# leds.net
KiCad netlist of a schematic drawn in EAGLE
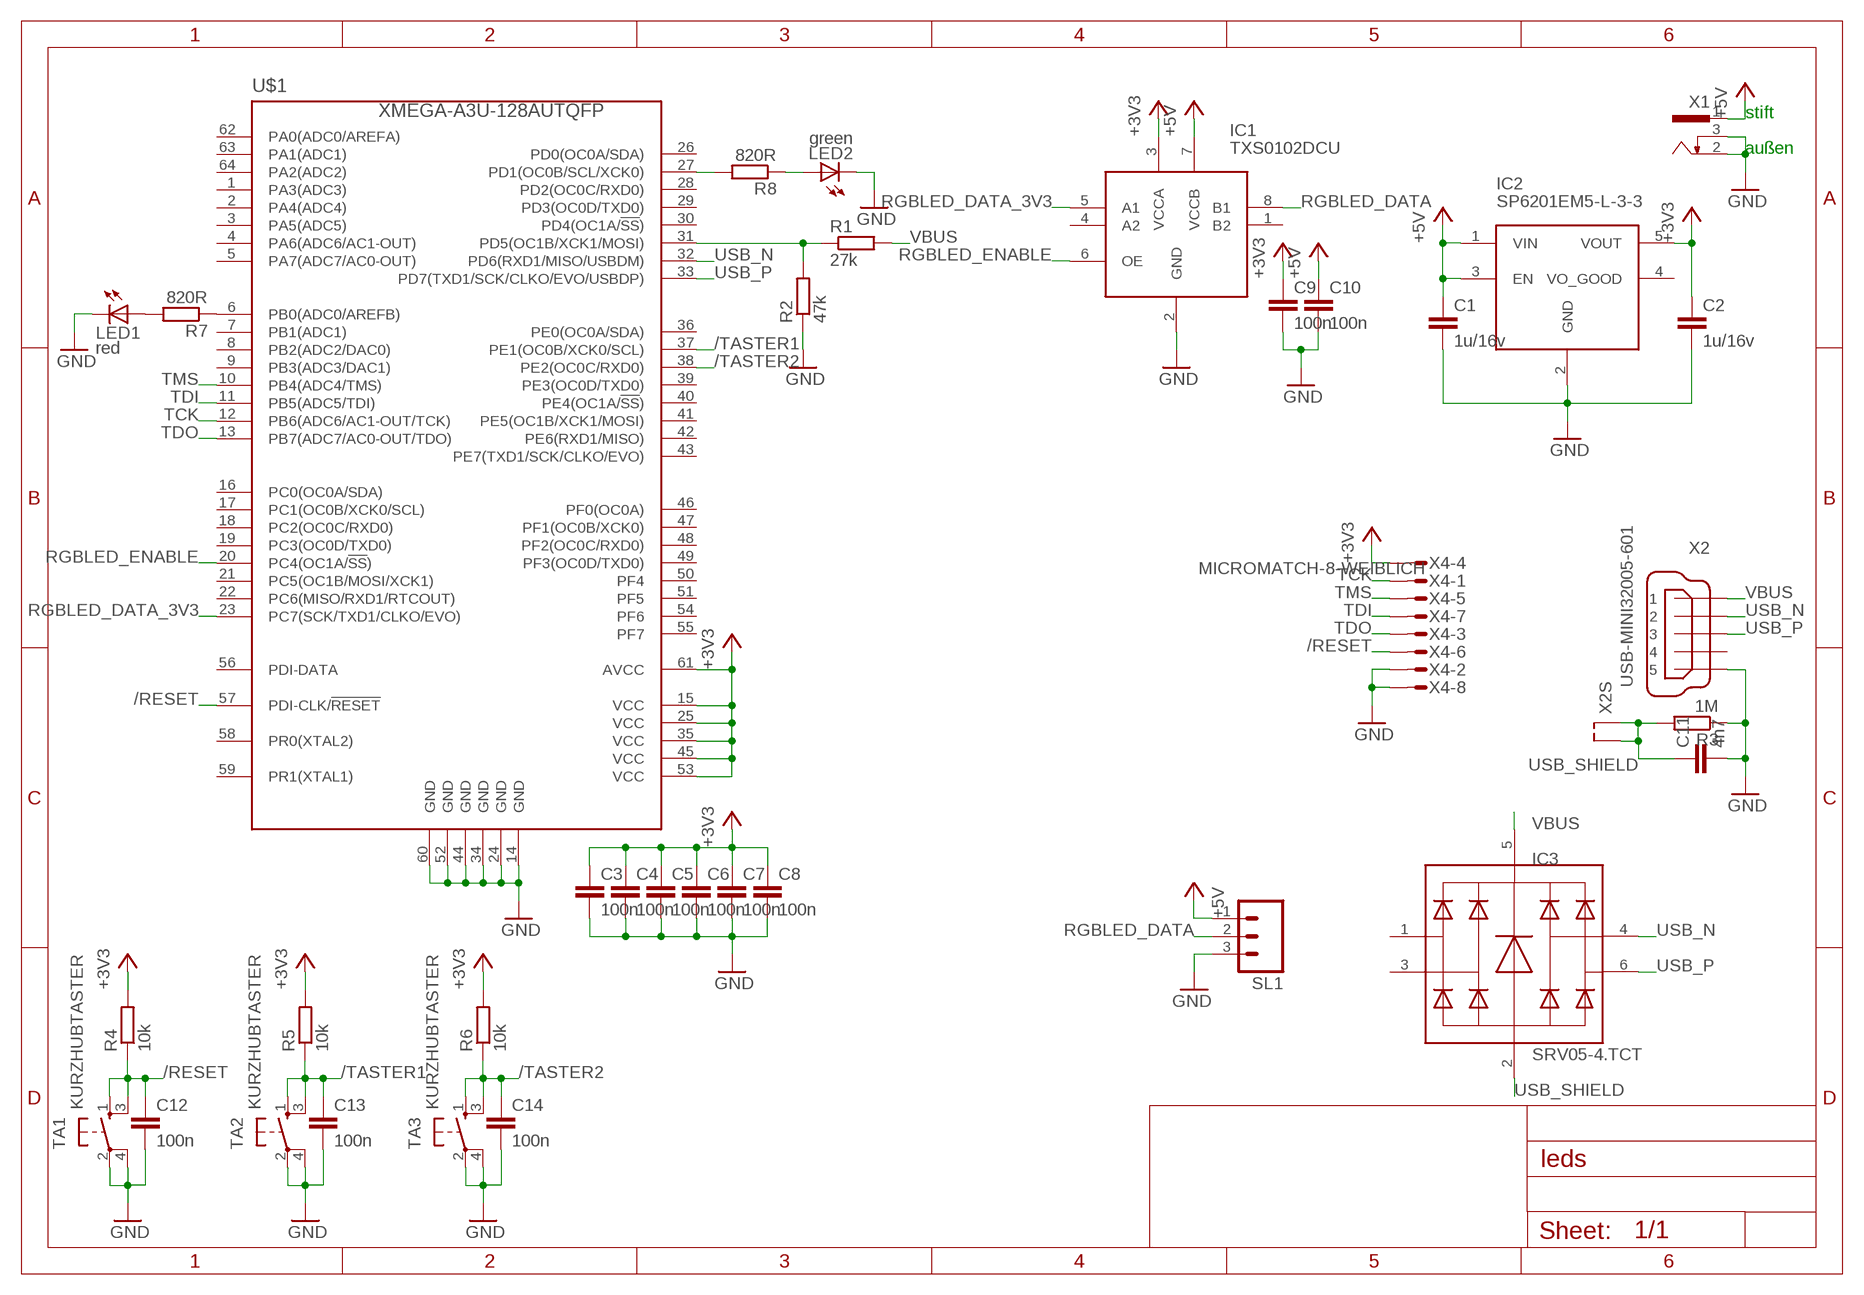
[diagram p0: schematic, sheet 1]

(export (version "E")
  (design (tool "Eeschema 10.0.6"))
  (components
    (comp (ref "C1")
      (value "1u/16v")
      (footprint "eagle-import:C0603")
      (libsource (lib "eagle-import") (part "C-EUC0603"))
    )
    (comp (ref "C2")
      (value "1u/16v")
      (footprint "eagle-import:C0603")
      (libsource (lib "eagle-import") (part "C-EUC0603"))
    )
    (comp (ref "C3")
      (value "100n")
      (footprint "eagle-import:C0603")
      (libsource (lib "eagle-import") (part "C-EUC0603"))
    )
    (comp (ref "C4")
      (value "100n")
      (footprint "eagle-import:C0603")
      (libsource (lib "eagle-import") (part "C-EUC0603"))
    )
    (comp (ref "C5")
      (value "100n")
      (footprint "eagle-import:C0603")
      (libsource (lib "eagle-import") (part "C-EUC0603"))
    )
    (comp (ref "C6")
      (value "100n")
      (footprint "eagle-import:C0603")
      (libsource (lib "eagle-import") (part "C-EUC0603"))
    )
    (comp (ref "C7")
      (value "100n")
      (footprint "eagle-import:C0603")
      (libsource (lib "eagle-import") (part "C-EUC0603"))
    )
    (comp (ref "C8")
      (value "100n")
      (footprint "eagle-import:C0603")
      (libsource (lib "eagle-import") (part "C-EUC0603"))
    )
    (comp (ref "C9")
      (value "100n")
      (footprint "eagle-import:C0603")
      (libsource (lib "eagle-import") (part "C-EUC0603"))
    )
    (comp (ref "C10")
      (value "100n")
      (footprint "eagle-import:C0603")
      (libsource (lib "eagle-import") (part "C-EUC0603"))
    )
    (comp (ref "C11")
      (value "4n7")
      (footprint "eagle-import:C0603")
      (libsource (lib "eagle-import") (part "C-EUC0603"))
    )
    (comp (ref "C12")
      (value "100n")
      (footprint "eagle-import:C0603")
      (libsource (lib "eagle-import") (part "C-EUC0603"))
    )
    (comp (ref "C13")
      (value "100n")
      (footprint "eagle-import:C0603")
      (libsource (lib "eagle-import") (part "C-EUC0603"))
    )
    (comp (ref "C14")
      (value "100n")
      (footprint "eagle-import:C0603")
      (libsource (lib "eagle-import") (part "C-EUC0603"))
    )
    (comp (ref "IC1")
      (value "TXS0102DCU")
      (footprint "eagle-import:DCU8")
      (libsource (lib "eagle-import") (part "TXS0102DCU"))
    )
    (comp (ref "IC2")
      (value "SP6201EM5-L-3-3")
      (footprint "eagle-import:SOT23-5")
      (libsource (lib "eagle-import") (part "SP6201EM5-L-3-3"))
    )
    (comp (ref "IC3")
      (value "SRV05-4.TCT")
      (footprint "eagle-import:SOT23-6")
      (libsource (lib "eagle-import") (part "SRV05-4.TCT"))
    )
    (comp (ref "LED1")
      (value "red")
      (footprint "eagle-import:CHIPLED_0603")
      (libsource (lib "eagle-import") (part "LEDCHIPLED_0603LR"))
    )
    (comp (ref "LED2")
      (value "green")
      (footprint "eagle-import:CHIPLED_0603")
      (libsource (lib "eagle-import") (part "LEDCHIPLED_0603LG"))
    )
    (comp (ref "R1")
      (value "27k")
      (footprint "eagle-import:R0603")
      (libsource (lib "eagle-import") (part "R-EU_R0603"))
    )
    (comp (ref "R2")
      (value "47k")
      (footprint "eagle-import:R0603")
      (libsource (lib "eagle-import") (part "R-EU_R0603"))
    )
    (comp (ref "R3")
      (value "1M")
      (footprint "eagle-import:R0603")
      (libsource (lib "eagle-import") (part "R-EU_R0603"))
    )
    (comp (ref "R4")
      (value "10k")
      (footprint "eagle-import:R0603")
      (libsource (lib "eagle-import") (part "R-EU_R0603"))
    )
    (comp (ref "R5")
      (value "10k")
      (footprint "eagle-import:R0603")
      (libsource (lib "eagle-import") (part "R-EU_R0603"))
    )
    (comp (ref "R6")
      (value "10k")
      (footprint "eagle-import:R0603")
      (libsource (lib "eagle-import") (part "R-EU_R0603"))
    )
    (comp (ref "R7")
      (value "820R")
      (footprint "eagle-import:R0603")
      (libsource (lib "eagle-import") (part "R-EU_R0603"))
    )
    (comp (ref "R8")
      (value "820R")
      (footprint "eagle-import:R0603")
      (libsource (lib "eagle-import") (part "R-EU_R0603"))
    )
    (comp (ref "SL1")
      (value "M03")
      (footprint "eagle-import:03P")
      (libsource (lib "eagle-import") (part "M03"))
    )
    (comp (ref "TA1")
      (value "KURZHUBTASTER")
      (footprint "eagle-import:TA93XX")
      (libsource (lib "eagle-import") (part "KURZHUBTASTER"))
    )
    (comp (ref "TA2")
      (value "KURZHUBTASTER")
      (footprint "eagle-import:TA93XX")
      (libsource (lib "eagle-import") (part "KURZHUBTASTER"))
    )
    (comp (ref "TA3")
      (value "KURZHUBTASTER")
      (footprint "eagle-import:TA93XX")
      (libsource (lib "eagle-import") (part "KURZHUBTASTER"))
    )
    (comp (ref "U$1")
      (value "XMEGA-A3U-128AUTQFP")
      (footprint "eagle-import:TQFP64")
      (libsource (lib "eagle-import") (part "XMEGA-A3UTQFP-128AU"))
    )
    (comp (ref "X1")
      (value "733980-62")
      (footprint "eagle-import:733980-62")
      (libsource (lib "eagle-import") (part "73398?0-62"))
    )
    (comp (ref "X2")
      (value "USB-MINI32005-601")
      (footprint "eagle-import:32005-601")
      (libsource (lib "eagle-import") (part "USB-MINI32005-601"))
    )
    (comp (ref "X4")
      (value "MICROMATCH-8-WEIBLICH")
      (footprint "eagle-import:MICROMATCH-8")
      (libsource (lib "eagle-import") (part "MICROMATCH-8-WEIBLICH"))
    )
  )
  (nets
    (net (code "1") (name "+3V3") (class "Default")
      (node (ref "C2") (pin "1") (pinfunction "1_1") (pintype "passive"))
      (node (ref "C3") (pin "1") (pinfunction "1_1") (pintype "passive"))
      (node (ref "C4") (pin "1") (pinfunction "1_1") (pintype "passive"))
      (node (ref "C5") (pin "1") (pinfunction "1_1") (pintype "passive"))
      (node (ref "C6") (pin "1") (pinfunction "1_1") (pintype "passive"))
      (node (ref "C7") (pin "1") (pinfunction "1_1") (pintype "passive"))
      (node (ref "C8") (pin "1") (pinfunction "1_1") (pintype "passive"))
      (node (ref "C9") (pin "1") (pinfunction "1_1") (pintype "passive"))
      (node (ref "IC1") (pin "3") (pinfunction "VCCA_3") (pintype "power_in"))
      (node (ref "IC2") (pin "5") (pinfunction "VOUT_5") (pintype "power_in"))
      (node (ref "R4") (pin "2") (pinfunction "2_2") (pintype "passive"))
      (node (ref "R5") (pin "2") (pinfunction "2_2") (pintype "passive"))
      (node (ref "R6") (pin "2") (pinfunction "2_2") (pintype "passive"))
      (node (ref "U$1") (pin "15") (pinfunction "VCC_15") (pintype "power_in"))
      (node (ref "U$1") (pin "25") (pinfunction "VCC_25") (pintype "power_in"))
      (node (ref "U$1") (pin "35") (pinfunction "VCC_35") (pintype "power_in"))
      (node (ref "U$1") (pin "45") (pinfunction "VCC_45") (pintype "power_in"))
      (node (ref "U$1") (pin "53") (pinfunction "VCC_53") (pintype "power_in"))
      (node (ref "U$1") (pin "61") (pinfunction "AVCC_61") (pintype "power_in"))
      (node (ref "X4") (pin "4") (pinfunction "S_4") (pintype "passive"))
    )
    (net (code "2") (name "+5V") (class "Default")
      (node (ref "C1") (pin "1") (pinfunction "1_1") (pintype "passive"))
      (node (ref "C10") (pin "1") (pinfunction "1_1") (pintype "passive"))
      (node (ref "IC1") (pin "7") (pinfunction "VCCB_7") (pintype "power_in"))
      (node (ref "IC2") (pin "1") (pinfunction "VIN_1") (pintype "power_in"))
      (node (ref "IC2") (pin "3") (pinfunction "EN_3") (pintype "input"))
      (node (ref "SL1") (pin "1") (pinfunction "1_1") (pintype "passive"))
      (node (ref "X1") (pin "1") (pinfunction "1_1") (pintype "passive"))
    )
    (net (code "3") (name "/RGBLED_DATA") (class "Default")
      (node (ref "IC1") (pin "8") (pinfunction "B1_8") (pintype "bidirectional"))
      (node (ref "SL1") (pin "2") (pinfunction "2_2") (pintype "passive"))
    )
    (net (code "4") (name "/RGBLED_DATA_3V3") (class "Default")
      (node (ref "IC1") (pin "5") (pinfunction "A1_5") (pintype "bidirectional"))
      (node (ref "U$1") (pin "23") (pinfunction "PC7(SCK/TXD1/CLKO/EVO)_23") (pintype "bidirectional"))
    )
    (net (code "5") (name "/RGBLED_ENABLE") (class "Default")
      (node (ref "IC1") (pin "6") (pinfunction "OE_6") (pintype "input"))
      (node (ref "U$1") (pin "20") (pinfunction "PC4(OC1A/~{SS})_20") (pintype "bidirectional"))
    )
    (net (code "6") (name "/TCK") (class "Default")
      (node (ref "U$1") (pin "12") (pinfunction "PB6(ADC6/AC1-OUT/TCK)_12") (pintype "bidirectional"))
      (node (ref "X4") (pin "1") (pinfunction "S_1") (pintype "passive"))
    )
    (net (code "7") (name "/TDI") (class "Default")
      (node (ref "U$1") (pin "11") (pinfunction "PB5(ADC5/TDI)_11") (pintype "bidirectional"))
      (node (ref "X4") (pin "7") (pinfunction "S_7") (pintype "passive"))
    )
    (net (code "8") (name "/TDO") (class "Default")
      (node (ref "U$1") (pin "13") (pinfunction "PB7(ADC7/AC0-OUT/TDO)_13") (pintype "bidirectional"))
      (node (ref "X4") (pin "3") (pinfunction "S_3") (pintype "passive"))
    )
    (net (code "9") (name "/TMS") (class "Default")
      (node (ref "U$1") (pin "10") (pinfunction "PB4(ADC4/TMS)_10") (pintype "bidirectional"))
      (node (ref "X4") (pin "5") (pinfunction "S_5") (pintype "passive"))
    )
    (net (code "10") (name "/USB_N") (class "Default")
      (node (ref "IC3") (pin "4") (pinfunction "3_4") (pintype "passive"))
      (node (ref "U$1") (pin "32") (pinfunction "PD6(RXD1/MISO/USBDM)_32") (pintype "bidirectional"))
      (node (ref "X2") (pin "2") (pinfunction "2_2") (pintype "passive"))
    )
    (net (code "11") (name "/USB_P") (class "Default")
      (node (ref "IC3") (pin "6") (pinfunction "4_6") (pintype "passive"))
      (node (ref "U$1") (pin "33") (pinfunction "PD7(TXD1/SCK/CLKO/EVO/USBDP)_33") (pintype "bidirectional"))
      (node (ref "X2") (pin "3") (pinfunction "3_3") (pintype "passive"))
    )
    (net (code "12") (name "/USB_SHIELD") (class "Default")
      (node (ref "C11") (pin "1") (pinfunction "1_1") (pintype "passive"))
      (node (ref "IC3") (pin "2") (pinfunction "A_2") (pintype "passive"))
      (node (ref "R3") (pin "2") (pinfunction "2_2") (pintype "passive"))
      (node (ref "X2") (pin "M1") (pinfunction "S1_M1") (pintype "passive"))
      (node (ref "X2") (pin "M2") (pinfunction "S2_M2") (pintype "passive"))
    )
    (net (code "13") (name "/VBUS") (class "Default")
      (node (ref "IC3") (pin "5") (pinfunction "K_5") (pintype "passive"))
      (node (ref "R1") (pin "2") (pinfunction "2_2") (pintype "passive"))
      (node (ref "X2") (pin "1") (pinfunction "1_1") (pintype "passive"))
    )
    (net (code "14") (name "/{slash}RESET") (class "Default")
      (node (ref "C12") (pin "1") (pinfunction "1_1") (pintype "passive"))
      (node (ref "R4") (pin "1") (pinfunction "1_1") (pintype "passive"))
      (node (ref "TA1") (pin "1") (pinfunction "S_1") (pintype "passive"))
      (node (ref "TA1") (pin "3") (pinfunction "S1_3") (pintype "passive"))
      (node (ref "U$1") (pin "57") (pinfunction "PDI-CLK/~{RESET}_57") (pintype "input"))
      (node (ref "X4") (pin "6") (pinfunction "S_6") (pintype "passive"))
    )
    (net (code "15") (name "/{slash}TASTER1") (class "Default")
      (node (ref "C13") (pin "1") (pinfunction "1_1") (pintype "passive"))
      (node (ref "R5") (pin "1") (pinfunction "1_1") (pintype "passive"))
      (node (ref "TA2") (pin "1") (pinfunction "S_1") (pintype "passive"))
      (node (ref "TA2") (pin "3") (pinfunction "S1_3") (pintype "passive"))
      (node (ref "U$1") (pin "37") (pinfunction "PE1(OC0B/XCK0/SCL)_37") (pintype "bidirectional"))
    )
    (net (code "16") (name "/{slash}TASTER2") (class "Default")
      (node (ref "C14") (pin "1") (pinfunction "1_1") (pintype "passive"))
      (node (ref "R6") (pin "1") (pinfunction "1_1") (pintype "passive"))
      (node (ref "TA3") (pin "1") (pinfunction "S_1") (pintype "passive"))
      (node (ref "TA3") (pin "3") (pinfunction "S1_3") (pintype "passive"))
      (node (ref "U$1") (pin "38") (pinfunction "PE2(OC0C/RXD0)_38") (pintype "bidirectional"))
    )
    (net (code "17") (name "GND") (class "Default")
      (node (ref "C1") (pin "2") (pinfunction "2_2") (pintype "passive"))
      (node (ref "C10") (pin "2") (pinfunction "2_2") (pintype "passive"))
      (node (ref "C11") (pin "2") (pinfunction "2_2") (pintype "passive"))
      (node (ref "C12") (pin "2") (pinfunction "2_2") (pintype "passive"))
      (node (ref "C13") (pin "2") (pinfunction "2_2") (pintype "passive"))
      (node (ref "C14") (pin "2") (pinfunction "2_2") (pintype "passive"))
      (node (ref "C2") (pin "2") (pinfunction "2_2") (pintype "passive"))
      (node (ref "C3") (pin "2") (pinfunction "2_2") (pintype "passive"))
      (node (ref "C4") (pin "2") (pinfunction "2_2") (pintype "passive"))
      (node (ref "C5") (pin "2") (pinfunction "2_2") (pintype "passive"))
      (node (ref "C6") (pin "2") (pinfunction "2_2") (pintype "passive"))
      (node (ref "C7") (pin "2") (pinfunction "2_2") (pintype "passive"))
      (node (ref "C8") (pin "2") (pinfunction "2_2") (pintype "passive"))
      (node (ref "C9") (pin "2") (pinfunction "2_2") (pintype "passive"))
      (node (ref "IC1") (pin "2") (pinfunction "GND_2") (pintype "power_in"))
      (node (ref "IC2") (pin "2") (pinfunction "GND_2") (pintype "power_in"))
      (node (ref "LED1") (pin "C") (pinfunction "C_C") (pintype "passive"))
      (node (ref "LED2") (pin "C") (pinfunction "C_C") (pintype "passive"))
      (node (ref "R2") (pin "1") (pinfunction "1_1") (pintype "passive"))
      (node (ref "R3") (pin "1") (pinfunction "1_1") (pintype "passive"))
      (node (ref "SL1") (pin "3") (pinfunction "3_3") (pintype "passive"))
      (node (ref "TA1") (pin "2") (pinfunction "P_2") (pintype "passive"))
      (node (ref "TA1") (pin "4") (pinfunction "P1_4") (pintype "passive"))
      (node (ref "TA2") (pin "2") (pinfunction "P_2") (pintype "passive"))
      (node (ref "TA2") (pin "4") (pinfunction "P1_4") (pintype "passive"))
      (node (ref "TA3") (pin "2") (pinfunction "P_2") (pintype "passive"))
      (node (ref "TA3") (pin "4") (pinfunction "P1_4") (pintype "passive"))
      (node (ref "U$1") (pin "14") (pinfunction "GND_14") (pintype "power_in"))
      (node (ref "U$1") (pin "24") (pinfunction "GND_24") (pintype "power_in"))
      (node (ref "U$1") (pin "34") (pinfunction "GND_34") (pintype "power_in"))
      (node (ref "U$1") (pin "44") (pinfunction "GND_44") (pintype "power_in"))
      (node (ref "U$1") (pin "52") (pinfunction "GND_52") (pintype "power_in"))
      (node (ref "U$1") (pin "60") (pinfunction "GND_60") (pintype "power_in"))
      (node (ref "X1") (pin "2") (pinfunction "2_2") (pintype "passive"))
      (node (ref "X1") (pin "3") (pinfunction "3_3") (pintype "passive"))
      (node (ref "X2") (pin "5") (pinfunction "5_5") (pintype "passive"))
      (node (ref "X4") (pin "2") (pinfunction "S_2") (pintype "passive"))
      (node (ref "X4") (pin "8") (pinfunction "S_8") (pintype "passive"))
    )
    (net (code "18") (name "Net-(LED1-PadA)") (class "Default")
      (node (ref "LED1") (pin "A") (pinfunction "A_A") (pintype "passive"))
      (node (ref "R7") (pin "2") (pinfunction "2_2") (pintype "passive"))
    )
    (net (code "19") (name "Net-(LED2-PadA)") (class "Default")
      (node (ref "LED2") (pin "A") (pinfunction "A_A") (pintype "passive"))
      (node (ref "R8") (pin "1") (pinfunction "1_1") (pintype "passive"))
    )
    (net (code "20") (name "Net-(U$1-PB0(ADC0{slash}AREFB))") (class "Default")
      (node (ref "R7") (pin "1") (pinfunction "1_1") (pintype "passive"))
      (node (ref "U$1") (pin "6") (pinfunction "PB0(ADC0/AREFB)_6") (pintype "bidirectional"))
    )
    (net (code "21") (name "Net-(U$1-PD1(OC0B{slash}SCL{slash}XCK0))") (class "Default")
      (node (ref "R8") (pin "2") (pinfunction "2_2") (pintype "passive"))
      (node (ref "U$1") (pin "27") (pinfunction "PD1(OC0B/SCL/XCK0)_27") (pintype "bidirectional"))
    )
    (net (code "22") (name "Net-(U$1-PD5(OC1B{slash}XCK1{slash}MOSI))") (class "Default")
      (node (ref "R1") (pin "1") (pinfunction "1_1") (pintype "passive"))
      (node (ref "R2") (pin "2") (pinfunction "2_2") (pintype "passive"))
      (node (ref "U$1") (pin "31") (pinfunction "PD5(OC1B/XCK1/MOSI)_31") (pintype "bidirectional"))
    )
    (net (code "23") (name "unconnected-(IC1-A2-Pad4)") (class "Default")
      (node (ref "IC1") (pin "4") (pinfunction "A2_4") (pintype "bidirectional"))
    )
    (net (code "24") (name "unconnected-(IC1-B2-Pad1)") (class "Default")
      (node (ref "IC1") (pin "1") (pinfunction "B2_1") (pintype "bidirectional"))
    )
    (net (code "25") (name "unconnected-(IC2-VO_GOOD-Pad4)") (class "Default")
      (node (ref "IC2") (pin "4") (pinfunction "VO_GOOD_4") (pintype "output"))
    )
    (net (code "26") (name "unconnected-(IC3-2-Pad3)") (class "Default")
      (node (ref "IC3") (pin "3") (pinfunction "2_3") (pintype "passive"))
    )
    (net (code "27") (name "unconnected-(IC3-Pad1)") (class "Default")
      (node (ref "IC3") (pin "1") (pinfunction "1_1") (pintype "passive"))
    )
    (net (code "28") (name "unconnected-(U$1-PA0(ADC0{slash}AREFA)-Pad62)") (class "Default")
      (node (ref "U$1") (pin "62") (pinfunction "PA0(ADC0/AREFA)_62") (pintype "bidirectional"))
    )
    (net (code "29") (name "unconnected-(U$1-PA1(ADC1)-Pad63)") (class "Default")
      (node (ref "U$1") (pin "63") (pinfunction "PA1(ADC1)_63") (pintype "bidirectional"))
    )
    (net (code "30") (name "unconnected-(U$1-PA2(ADC2)-Pad64)") (class "Default")
      (node (ref "U$1") (pin "64") (pinfunction "PA2(ADC2)_64") (pintype "bidirectional"))
    )
    (net (code "31") (name "unconnected-(U$1-PA3(ADC3)-Pad1)") (class "Default")
      (node (ref "U$1") (pin "1") (pinfunction "PA3(ADC3)_1") (pintype "bidirectional"))
    )
    (net (code "32") (name "unconnected-(U$1-PA4(ADC4)-Pad2)") (class "Default")
      (node (ref "U$1") (pin "2") (pinfunction "PA4(ADC4)_2") (pintype "bidirectional"))
    )
    (net (code "33") (name "unconnected-(U$1-PA5(ADC5)-Pad3)") (class "Default")
      (node (ref "U$1") (pin "3") (pinfunction "PA5(ADC5)_3") (pintype "bidirectional"))
    )
    (net (code "34") (name "unconnected-(U$1-PA6(ADC6{slash}AC1-OUT)-Pad4)") (class "Default")
      (node (ref "U$1") (pin "4") (pinfunction "PA6(ADC6/AC1-OUT)_4") (pintype "bidirectional"))
    )
    (net (code "35") (name "unconnected-(U$1-PA7(ADC7{slash}AC0-OUT)-Pad5)") (class "Default")
      (node (ref "U$1") (pin "5") (pinfunction "PA7(ADC7/AC0-OUT)_5") (pintype "bidirectional"))
    )
    (net (code "36") (name "unconnected-(U$1-PB1(ADC1)-Pad7)") (class "Default")
      (node (ref "U$1") (pin "7") (pinfunction "PB1(ADC1)_7") (pintype "bidirectional"))
    )
    (net (code "37") (name "unconnected-(U$1-PB2(ADC2{slash}DAC0)-Pad8)") (class "Default")
      (node (ref "U$1") (pin "8") (pinfunction "PB2(ADC2/DAC0)_8") (pintype "bidirectional"))
    )
    (net (code "38") (name "unconnected-(U$1-PB3(ADC3{slash}DAC1)-Pad9)") (class "Default")
      (node (ref "U$1") (pin "9") (pinfunction "PB3(ADC3/DAC1)_9") (pintype "bidirectional"))
    )
    (net (code "39") (name "unconnected-(U$1-PC0(OC0A{slash}SDA)-Pad16)") (class "Default")
      (node (ref "U$1") (pin "16") (pinfunction "PC0(OC0A/SDA)_16") (pintype "bidirectional"))
    )
    (net (code "40") (name "unconnected-(U$1-PC1(OC0B{slash}XCK0{slash}SCL)-Pad17)") (class "Default")
      (node (ref "U$1") (pin "17") (pinfunction "PC1(OC0B/XCK0/SCL)_17") (pintype "bidirectional"))
    )
    (net (code "41") (name "unconnected-(U$1-PC2(OC0C{slash}RXD0)-Pad18)") (class "Default")
      (node (ref "U$1") (pin "18") (pinfunction "PC2(OC0C/RXD0)_18") (pintype "bidirectional"))
    )
    (net (code "42") (name "unconnected-(U$1-PC3(OC0D{slash}TXD0)-Pad19)") (class "Default")
      (node (ref "U$1") (pin "19") (pinfunction "PC3(OC0D/TXD0)_19") (pintype "bidirectional"))
    )
    (net (code "43") (name "unconnected-(U$1-PC5(OC1B{slash}MOSI{slash}XCK1)-Pad21)") (class "Default")
      (node (ref "U$1") (pin "21") (pinfunction "PC5(OC1B/MOSI/XCK1)_21") (pintype "bidirectional"))
    )
    (net (code "44") (name "unconnected-(U$1-PC6(MISO{slash}RXD1{slash}RTCOUT)-Pad22)") (class "Default")
      (node (ref "U$1") (pin "22") (pinfunction "PC6(MISO/RXD1/RTCOUT)_22") (pintype "bidirectional"))
    )
    (net (code "45") (name "unconnected-(U$1-PD0(OC0A{slash}SDA)-Pad26)") (class "Default")
      (node (ref "U$1") (pin "26") (pinfunction "PD0(OC0A/SDA)_26") (pintype "bidirectional"))
    )
    (net (code "46") (name "unconnected-(U$1-PD2(OC0C{slash}RXD0)-Pad28)") (class "Default")
      (node (ref "U$1") (pin "28") (pinfunction "PD2(OC0C/RXD0)_28") (pintype "bidirectional"))
    )
    (net (code "47") (name "unconnected-(U$1-PD3(OC0D{slash}TXD0)-Pad29)") (class "Default")
      (node (ref "U$1") (pin "29") (pinfunction "PD3(OC0D/TXD0)_29") (pintype "bidirectional"))
    )
    (net (code "48") (name "unconnected-(U$1-PD4(OC1A{slash}~{SS})-Pad30)") (class "Default")
      (node (ref "U$1") (pin "30") (pinfunction "PD4(OC1A/~{SS})_30") (pintype "bidirectional"))
    )
    (net (code "49") (name "unconnected-(U$1-PDI-DATA-Pad56)") (class "Default")
      (node (ref "U$1") (pin "56") (pinfunction "PDI-DATA_56") (pintype "bidirectional"))
    )
    (net (code "50") (name "unconnected-(U$1-PE0(OC0A{slash}SDA)-Pad36)") (class "Default")
      (node (ref "U$1") (pin "36") (pinfunction "PE0(OC0A/SDA)_36") (pintype "bidirectional"))
    )
    (net (code "51") (name "unconnected-(U$1-PE3(OC0D{slash}TXD0)-Pad39)") (class "Default")
      (node (ref "U$1") (pin "39") (pinfunction "PE3(OC0D/TXD0)_39") (pintype "bidirectional"))
    )
    (net (code "52") (name "unconnected-(U$1-PE4(OC1A{slash}~{SS})-Pad40)") (class "Default")
      (node (ref "U$1") (pin "40") (pinfunction "PE4(OC1A/~{SS})_40") (pintype "bidirectional"))
    )
    (net (code "53") (name "unconnected-(U$1-PE5(OC1B{slash}XCK1{slash}MOSI)-Pad41)") (class "Default")
      (node (ref "U$1") (pin "41") (pinfunction "PE5(OC1B/XCK1/MOSI)_41") (pintype "bidirectional"))
    )
    (net (code "54") (name "unconnected-(U$1-PE6(RXD1{slash}MISO)-Pad42)") (class "Default")
      (node (ref "U$1") (pin "42") (pinfunction "PE6(RXD1/MISO)_42") (pintype "bidirectional"))
    )
    (net (code "55") (name "unconnected-(U$1-PE7(TXD1{slash}SCK{slash}CLKO{slash}EVO)-Pad43)") (class "Default")
      (node (ref "U$1") (pin "43") (pinfunction "PE7(TXD1/SCK/CLKO/EVO)_43") (pintype "bidirectional"))
    )
    (net (code "56") (name "unconnected-(U$1-PF0(OC0A)-Pad46)") (class "Default")
      (node (ref "U$1") (pin "46") (pinfunction "PF0(OC0A)_46") (pintype "bidirectional"))
    )
    (net (code "57") (name "unconnected-(U$1-PF1(OC0B{slash}XCK0)-Pad47)") (class "Default")
      (node (ref "U$1") (pin "47") (pinfunction "PF1(OC0B/XCK0)_47") (pintype "bidirectional"))
    )
    (net (code "58") (name "unconnected-(U$1-PF2(OC0C{slash}RXD0)-Pad48)") (class "Default")
      (node (ref "U$1") (pin "48") (pinfunction "PF2(OC0C/RXD0)_48") (pintype "bidirectional"))
    )
    (net (code "59") (name "unconnected-(U$1-PF3(OC0D{slash}TXD0)-Pad49)") (class "Default")
      (node (ref "U$1") (pin "49") (pinfunction "PF3(OC0D/TXD0)_49") (pintype "bidirectional"))
    )
    (net (code "60") (name "unconnected-(U$1-PF4-Pad50)") (class "Default")
      (node (ref "U$1") (pin "50") (pinfunction "PF4_50") (pintype "bidirectional"))
    )
    (net (code "61") (name "unconnected-(U$1-PF5-Pad51)") (class "Default")
      (node (ref "U$1") (pin "51") (pinfunction "PF5_51") (pintype "bidirectional"))
    )
    (net (code "62") (name "unconnected-(U$1-PF6-Pad54)") (class "Default")
      (node (ref "U$1") (pin "54") (pinfunction "PF6_54") (pintype "bidirectional"))
    )
    (net (code "63") (name "unconnected-(U$1-PF7-Pad55)") (class "Default")
      (node (ref "U$1") (pin "55") (pinfunction "PF7_55") (pintype "bidirectional"))
    )
    (net (code "64") (name "unconnected-(U$1-PR0(XTAL2)-Pad58)") (class "Default")
      (node (ref "U$1") (pin "58") (pinfunction "PR0(XTAL2)_58") (pintype "bidirectional"))
    )
    (net (code "65") (name "unconnected-(U$1-PR1(XTAL1)-Pad59)") (class "Default")
      (node (ref "U$1") (pin "59") (pinfunction "PR1(XTAL1)_59") (pintype "bidirectional"))
    )
    (net (code "66") (name "unconnected-(X2-Pad4)") (class "Default")
      (node (ref "X2") (pin "4") (pinfunction "4_4") (pintype "passive"))
    )
  )
)
